# TD_sch.net
KiCad netlist of a schematic drawn in Altium Designer
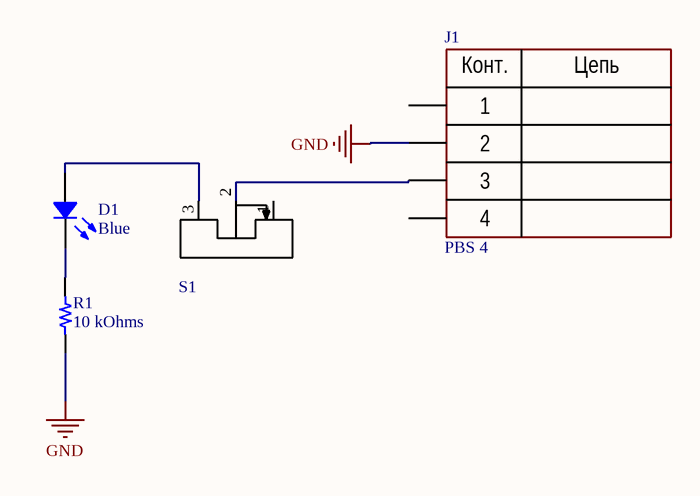
[diagram p0: TD_sch.SchDoc]

(export (version "E")
  (design (tool "Eeschema 10.0.6"))
  (components
    (comp (ref "D1")
      (value "Blue")
      (footprint "LED 1206_3216 BLUE")
      (description "LED BLUE CLEAR SMD")
      (fields
        (field (name "PART NUMBER") "SML-LXLC1206USBCTR")
        (field (name "MANUFACTURER") "Lumex Opto/Components Inc.")
      )
      (libsource (lib "Celestial Altium Library - altium_library") (part "LED"))
    )
    (comp (ref "J1") (value "PBS 4") (footprint "PBS-4 CUT") (libsource (lib "liba") (part "PBS 4")))
    (comp (ref "R1")
      (value "10 kOhms")
      (footprint "RES 0603_1608")
      (description "RES 10K OHM 0.1% 1/16W 0603")
      (fields
        (field (name "PART NUMBER") "RNCS0603BKE10K0")
        (field (name "MANUFACTURER") "Stackpole Electronics Inc")
      )
      (libsource (lib "Celestial Altium Library - altium_library") (part "Resistor"))
    )
    (comp (ref "S1") (value "S1") (footprint "switcher") (libsource (lib "liba") (part "switcher")))
  )
  (nets
    (net (code "1") (name "GND") (class "Default")
      (node (ref "J1") (pin "2") (pinfunction "2_2") (pintype "passive"))
      (node (ref "R1") (pin "1") (pinfunction "1_1") (pintype "passive"))
    )
    (net (code "2") (name "Net-(D1-Pad1)") (class "Default")
      (node (ref "D1") (pin "1") (pinfunction "1_1") (pintype "passive"))
      (node (ref "S1") (pin "3") (pinfunction "3_3") (pintype "passive"))
    )
    (net (code "3") (name "Net-(D1-Pad2)") (class "Default")
      (node (ref "D1") (pin "2") (pinfunction "2_2") (pintype "passive"))
      (node (ref "R1") (pin "2") (pinfunction "2_2") (pintype "passive"))
    )
    (net (code "4") (name "Net-(J1-Pad3)") (class "Default")
      (node (ref "J1") (pin "3") (pinfunction "3_3") (pintype "passive"))
      (node (ref "S1") (pin "2") (pinfunction "2_2") (pintype "passive"))
    )
    (net (code "5") (name "unconnected-(J1-Pad1)") (class "Default")
      (node (ref "J1") (pin "1") (pinfunction "1_1") (pintype "passive"))
    )
    (net (code "6") (name "unconnected-(J1-Pad4)") (class "Default")
      (node (ref "J1") (pin "4") (pinfunction "4_4") (pintype "passive"))
    )
    (net (code "7") (name "unconnected-(S1-Pad1)") (class "Default")
      (node (ref "S1") (pin "1") (pinfunction "1_1") (pintype "passive"))
    )
  )
)
